# PlacaLEDS.net
KiCad netlist of a schematic drawn in EAGLE
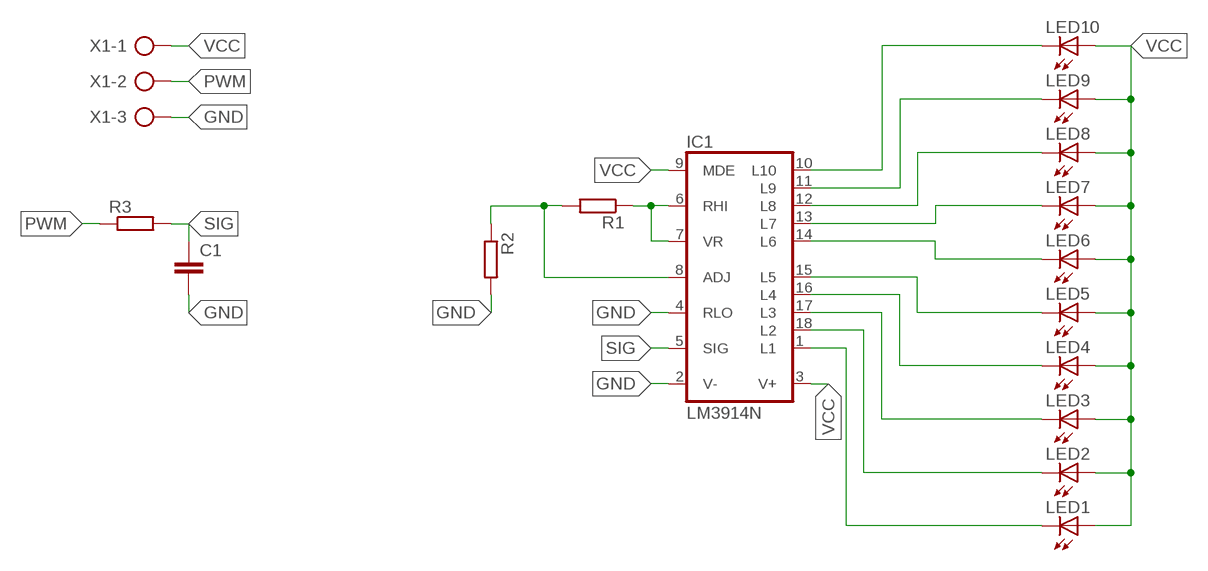
[diagram p0: schematic, sheet 1]

(export (version "E")
  (design (tool "Eeschema 10.0.6"))
  (components
    (comp (ref "C1")
      (value "C-EU025-050X050")
      (footprint "eagle-import:C025-050X050")
      (libsource (lib "eagle-import") (part "C-EU025-050X050"))
    )
    (comp (ref "IC1")
      (value "LM3914N")
      (footprint "eagle-import:DIL18")
      (libsource (lib "eagle-import") (part "LM3914N"))
    )
    (comp (ref "LED1")
      (value "LED5MM")
      (footprint "eagle-import:LED5MM")
      (libsource (lib "eagle-import") (part "LED5MM"))
    )
    (comp (ref "LED2")
      (value "LED5MM")
      (footprint "eagle-import:LED5MM")
      (libsource (lib "eagle-import") (part "LED5MM"))
    )
    (comp (ref "LED3")
      (value "LED5MM")
      (footprint "eagle-import:LED5MM")
      (libsource (lib "eagle-import") (part "LED5MM"))
    )
    (comp (ref "LED4")
      (value "LED5MM")
      (footprint "eagle-import:LED5MM")
      (libsource (lib "eagle-import") (part "LED5MM"))
    )
    (comp (ref "LED5")
      (value "LED5MM")
      (footprint "eagle-import:LED5MM")
      (libsource (lib "eagle-import") (part "LED5MM"))
    )
    (comp (ref "LED6")
      (value "LED5MM")
      (footprint "eagle-import:LED5MM")
      (libsource (lib "eagle-import") (part "LED5MM"))
    )
    (comp (ref "LED7")
      (value "LED5MM")
      (footprint "eagle-import:LED5MM")
      (libsource (lib "eagle-import") (part "LED5MM"))
    )
    (comp (ref "LED8")
      (value "LED5MM")
      (footprint "eagle-import:LED5MM")
      (libsource (lib "eagle-import") (part "LED5MM"))
    )
    (comp (ref "LED9")
      (value "LED5MM")
      (footprint "eagle-import:LED5MM")
      (libsource (lib "eagle-import") (part "LED5MM"))
    )
    (comp (ref "LED10")
      (value "LED5MM")
      (footprint "eagle-import:LED5MM")
      (libsource (lib "eagle-import") (part "LED5MM"))
    )
    (comp (ref "R1")
      (value "R-EU_0204/7")
      (footprint "eagle-import:0204_7")
      (libsource (lib "eagle-import") (part "R-EU_0204/7"))
    )
    (comp (ref "R2")
      (value "R-EU_0204/7")
      (footprint "eagle-import:0204_7")
      (libsource (lib "eagle-import") (part "R-EU_0204/7"))
    )
    (comp (ref "R3")
      (value "R-EU_0204/7")
      (footprint "eagle-import:0204_7")
      (libsource (lib "eagle-import") (part "R-EU_0204/7"))
    )
    (comp (ref "X1")
      (value "AK500/3")
      (footprint "eagle-import:AK500_3")
      (libsource (lib "eagle-import") (part "AK500/3"))
    )
  )
  (nets
    (net (code "1") (name "GND") (class "Default")
      (node (ref "C1") (pin "2") (pinfunction "2_2") (pintype "passive"))
      (node (ref "IC1") (pin "2") (pinfunction "V-_2") (pintype "power_in"))
      (node (ref "IC1") (pin "4") (pinfunction "RLO_4") (pintype "input"))
      (node (ref "R2") (pin "2") (pinfunction "2_2") (pintype "passive"))
      (node (ref "X1") (pin "3") (pinfunction "KL_3") (pintype "passive"))
    )
    (net (code "2") (name "Net-(IC1-ADJ)") (class "Default")
      (node (ref "IC1") (pin "8") (pinfunction "ADJ_8") (pintype "input"))
      (node (ref "R1") (pin "2") (pinfunction "2_2") (pintype "passive"))
      (node (ref "R2") (pin "1") (pinfunction "1_1") (pintype "passive"))
    )
    (net (code "3") (name "Net-(IC1-L1)") (class "Default")
      (node (ref "IC1") (pin "1") (pinfunction "L1_1") (pintype "output"))
      (node (ref "LED1") (pin "K") (pinfunction "C_K") (pintype "passive"))
    )
    (net (code "4") (name "Net-(IC1-L2)") (class "Default")
      (node (ref "IC1") (pin "18") (pinfunction "L2_18") (pintype "output"))
      (node (ref "LED2") (pin "K") (pinfunction "C_K") (pintype "passive"))
    )
    (net (code "5") (name "Net-(IC1-L3)") (class "Default")
      (node (ref "IC1") (pin "17") (pinfunction "L3_17") (pintype "output"))
      (node (ref "LED3") (pin "K") (pinfunction "C_K") (pintype "passive"))
    )
    (net (code "6") (name "Net-(IC1-L4)") (class "Default")
      (node (ref "IC1") (pin "16") (pinfunction "L4_16") (pintype "output"))
      (node (ref "LED4") (pin "K") (pinfunction "C_K") (pintype "passive"))
    )
    (net (code "7") (name "Net-(IC1-L5)") (class "Default")
      (node (ref "IC1") (pin "15") (pinfunction "L5_15") (pintype "output"))
      (node (ref "LED5") (pin "K") (pinfunction "C_K") (pintype "passive"))
    )
    (net (code "8") (name "Net-(IC1-L6)") (class "Default")
      (node (ref "IC1") (pin "14") (pinfunction "L6_14") (pintype "output"))
      (node (ref "LED6") (pin "K") (pinfunction "C_K") (pintype "passive"))
    )
    (net (code "9") (name "Net-(IC1-L7)") (class "Default")
      (node (ref "IC1") (pin "13") (pinfunction "L7_13") (pintype "output"))
      (node (ref "LED7") (pin "K") (pinfunction "C_K") (pintype "passive"))
    )
    (net (code "10") (name "Net-(IC1-L8)") (class "Default")
      (node (ref "IC1") (pin "12") (pinfunction "L8_12") (pintype "output"))
      (node (ref "LED8") (pin "K") (pinfunction "C_K") (pintype "passive"))
    )
    (net (code "11") (name "Net-(IC1-L9)") (class "Default")
      (node (ref "IC1") (pin "11") (pinfunction "L9_11") (pintype "output"))
      (node (ref "LED9") (pin "K") (pinfunction "C_K") (pintype "passive"))
    )
    (net (code "12") (name "Net-(IC1-L10)") (class "Default")
      (node (ref "IC1") (pin "10") (pinfunction "L10_10") (pintype "output"))
      (node (ref "LED10") (pin "K") (pinfunction "C_K") (pintype "passive"))
    )
    (net (code "13") (name "Net-(IC1-RHI)") (class "Default")
      (node (ref "IC1") (pin "6") (pinfunction "RHI_6") (pintype "input"))
      (node (ref "IC1") (pin "7") (pinfunction "VR_7") (pintype "output"))
      (node (ref "R1") (pin "1") (pinfunction "1_1") (pintype "passive"))
    )
    (net (code "14") (name "PWM") (class "Default")
      (node (ref "R3") (pin "1") (pinfunction "1_1") (pintype "passive"))
      (node (ref "X1") (pin "2") (pinfunction "KL_2") (pintype "passive"))
    )
    (net (code "15") (name "SIG") (class "Default")
      (node (ref "C1") (pin "1") (pinfunction "1_1") (pintype "passive"))
      (node (ref "IC1") (pin "5") (pinfunction "SIG_5") (pintype "input"))
      (node (ref "R3") (pin "2") (pinfunction "2_2") (pintype "passive"))
    )
    (net (code "16") (name "VCC") (class "Default")
      (node (ref "IC1") (pin "3") (pinfunction "V+_3") (pintype "power_in"))
      (node (ref "IC1") (pin "9") (pinfunction "MDE_9") (pintype "input"))
      (node (ref "LED1") (pin "A") (pinfunction "A_A") (pintype "passive"))
      (node (ref "LED10") (pin "A") (pinfunction "A_A") (pintype "passive"))
      (node (ref "LED2") (pin "A") (pinfunction "A_A") (pintype "passive"))
      (node (ref "LED3") (pin "A") (pinfunction "A_A") (pintype "passive"))
      (node (ref "LED4") (pin "A") (pinfunction "A_A") (pintype "passive"))
      (node (ref "LED5") (pin "A") (pinfunction "A_A") (pintype "passive"))
      (node (ref "LED6") (pin "A") (pinfunction "A_A") (pintype "passive"))
      (node (ref "LED7") (pin "A") (pinfunction "A_A") (pintype "passive"))
      (node (ref "LED8") (pin "A") (pinfunction "A_A") (pintype "passive"))
      (node (ref "LED9") (pin "A") (pinfunction "A_A") (pintype "passive"))
      (node (ref "X1") (pin "1") (pinfunction "KL_1") (pintype "passive"))
    )
  )
)
